# step_motor.net
KiCad netlist of a schematic drawn in EAGLE
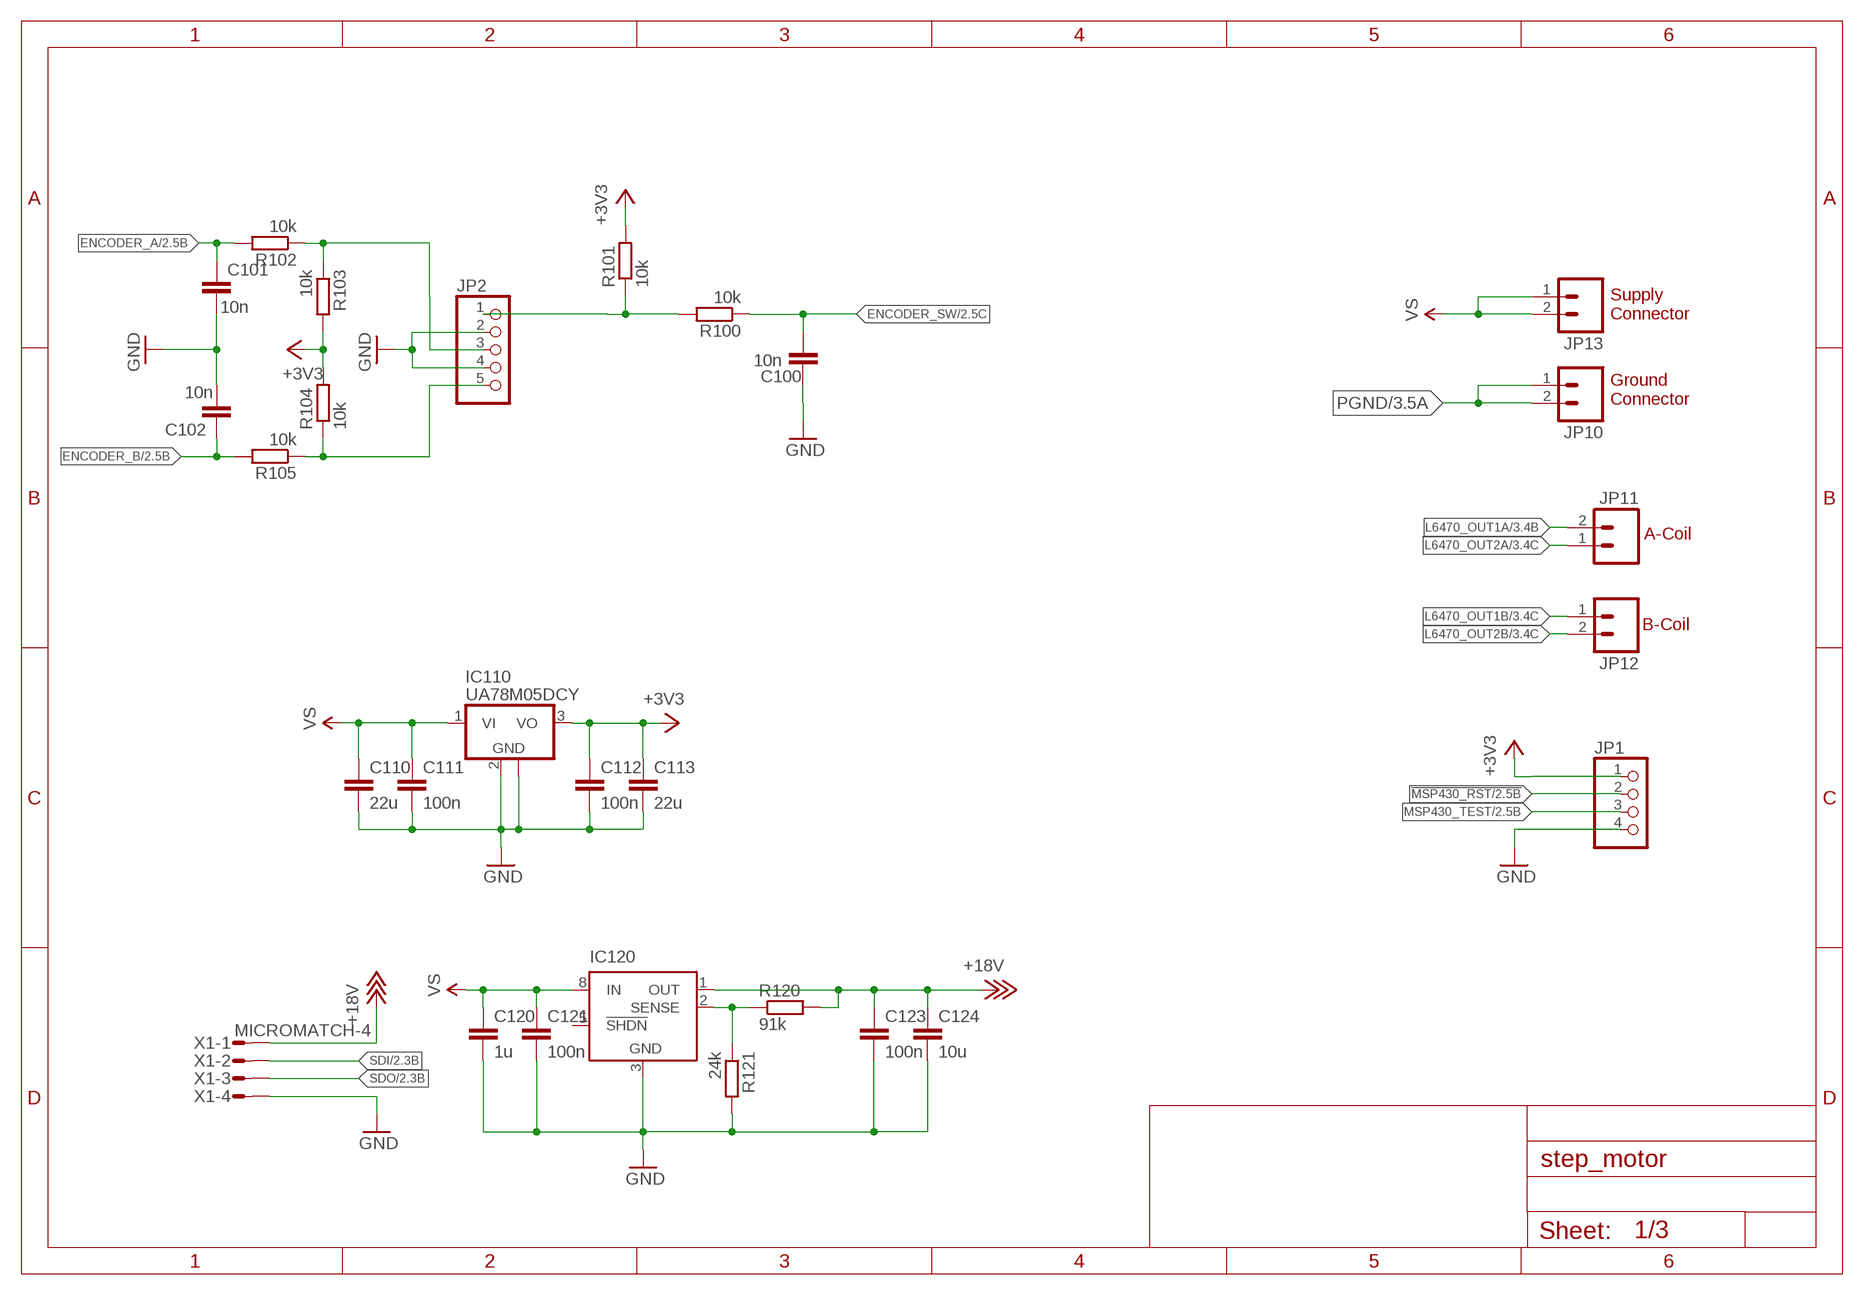
[diagram p0: schematic, sheet 1]
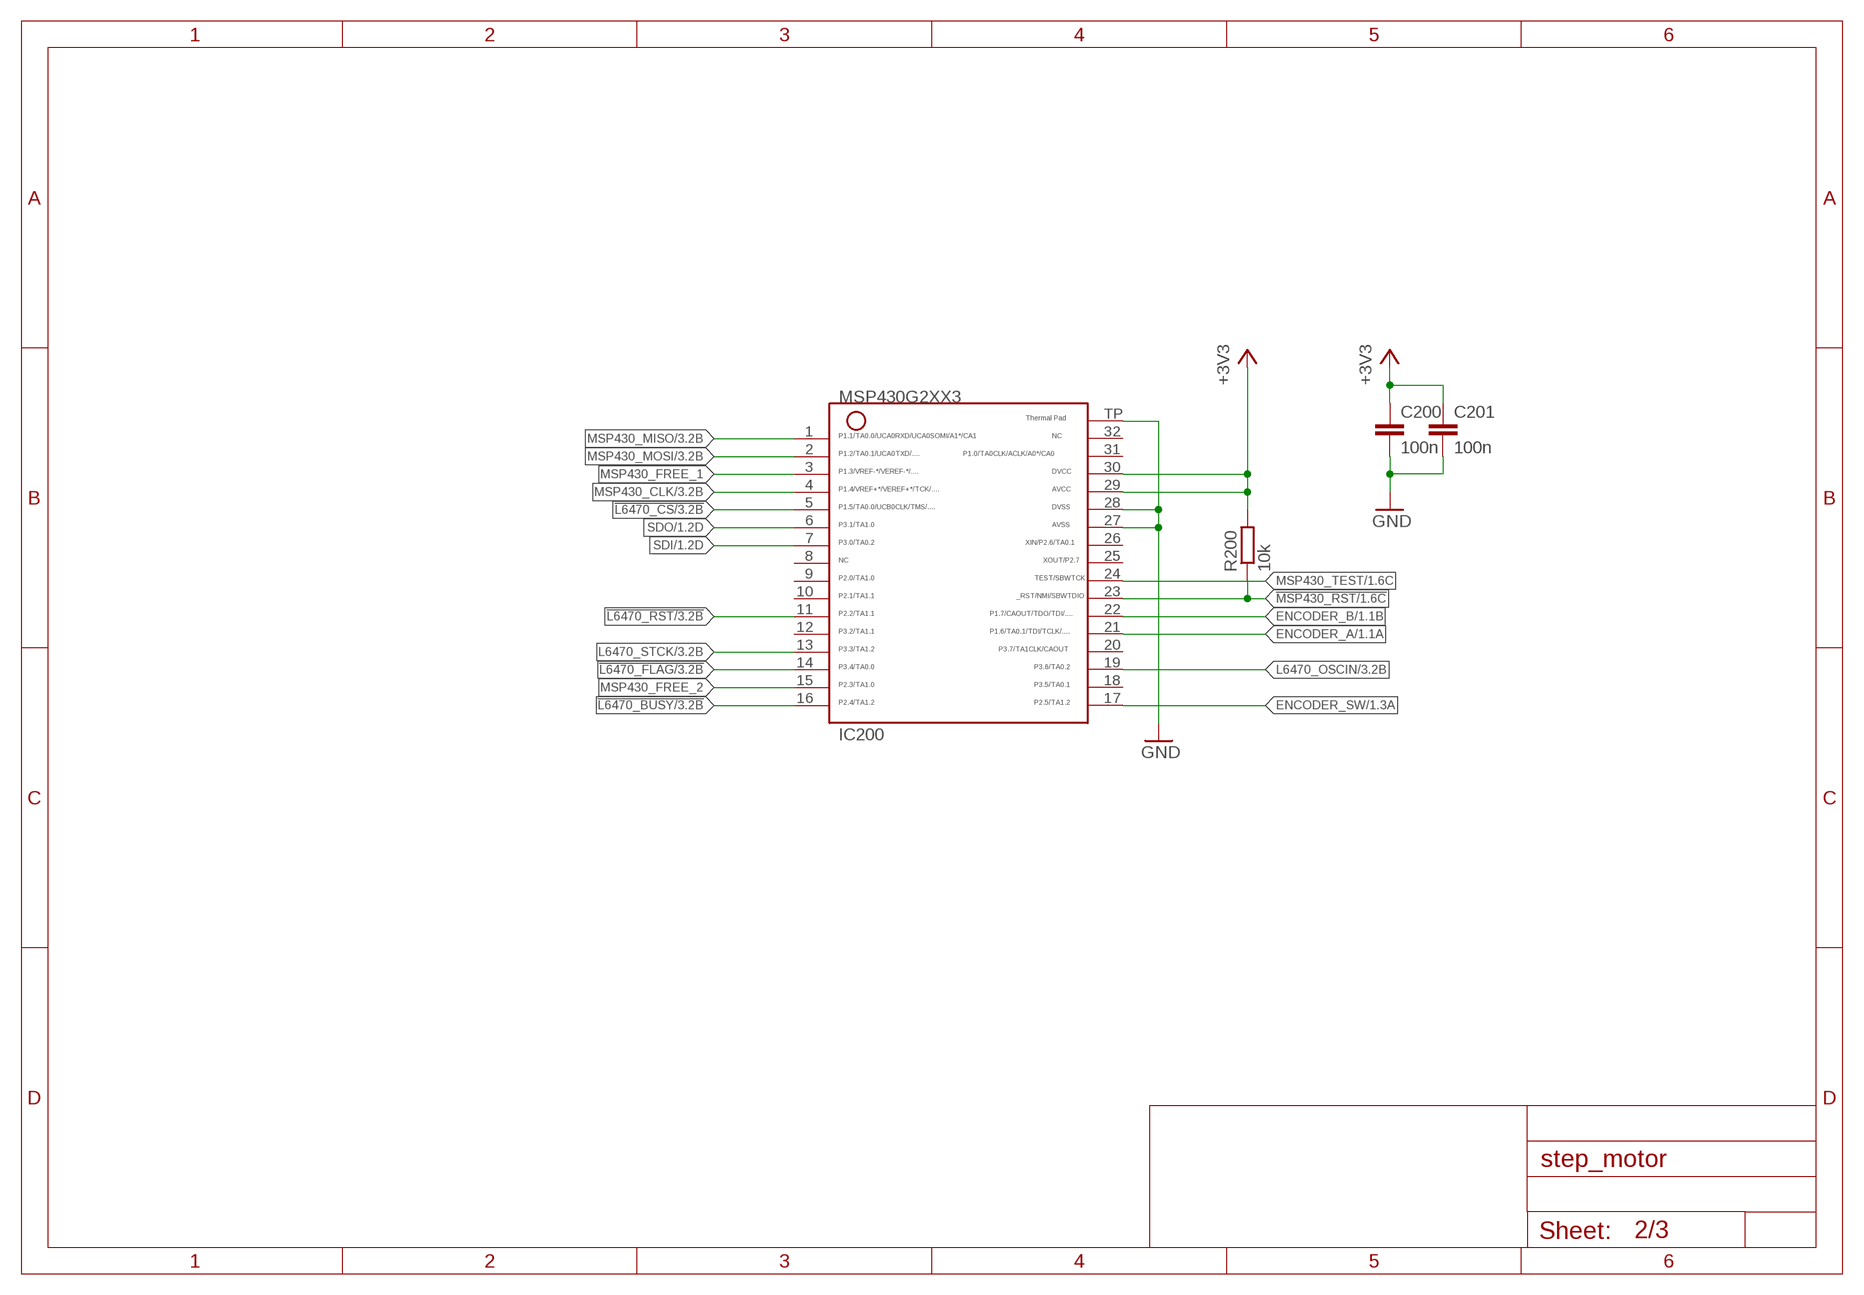
[diagram p1: schematic, sheet 2]
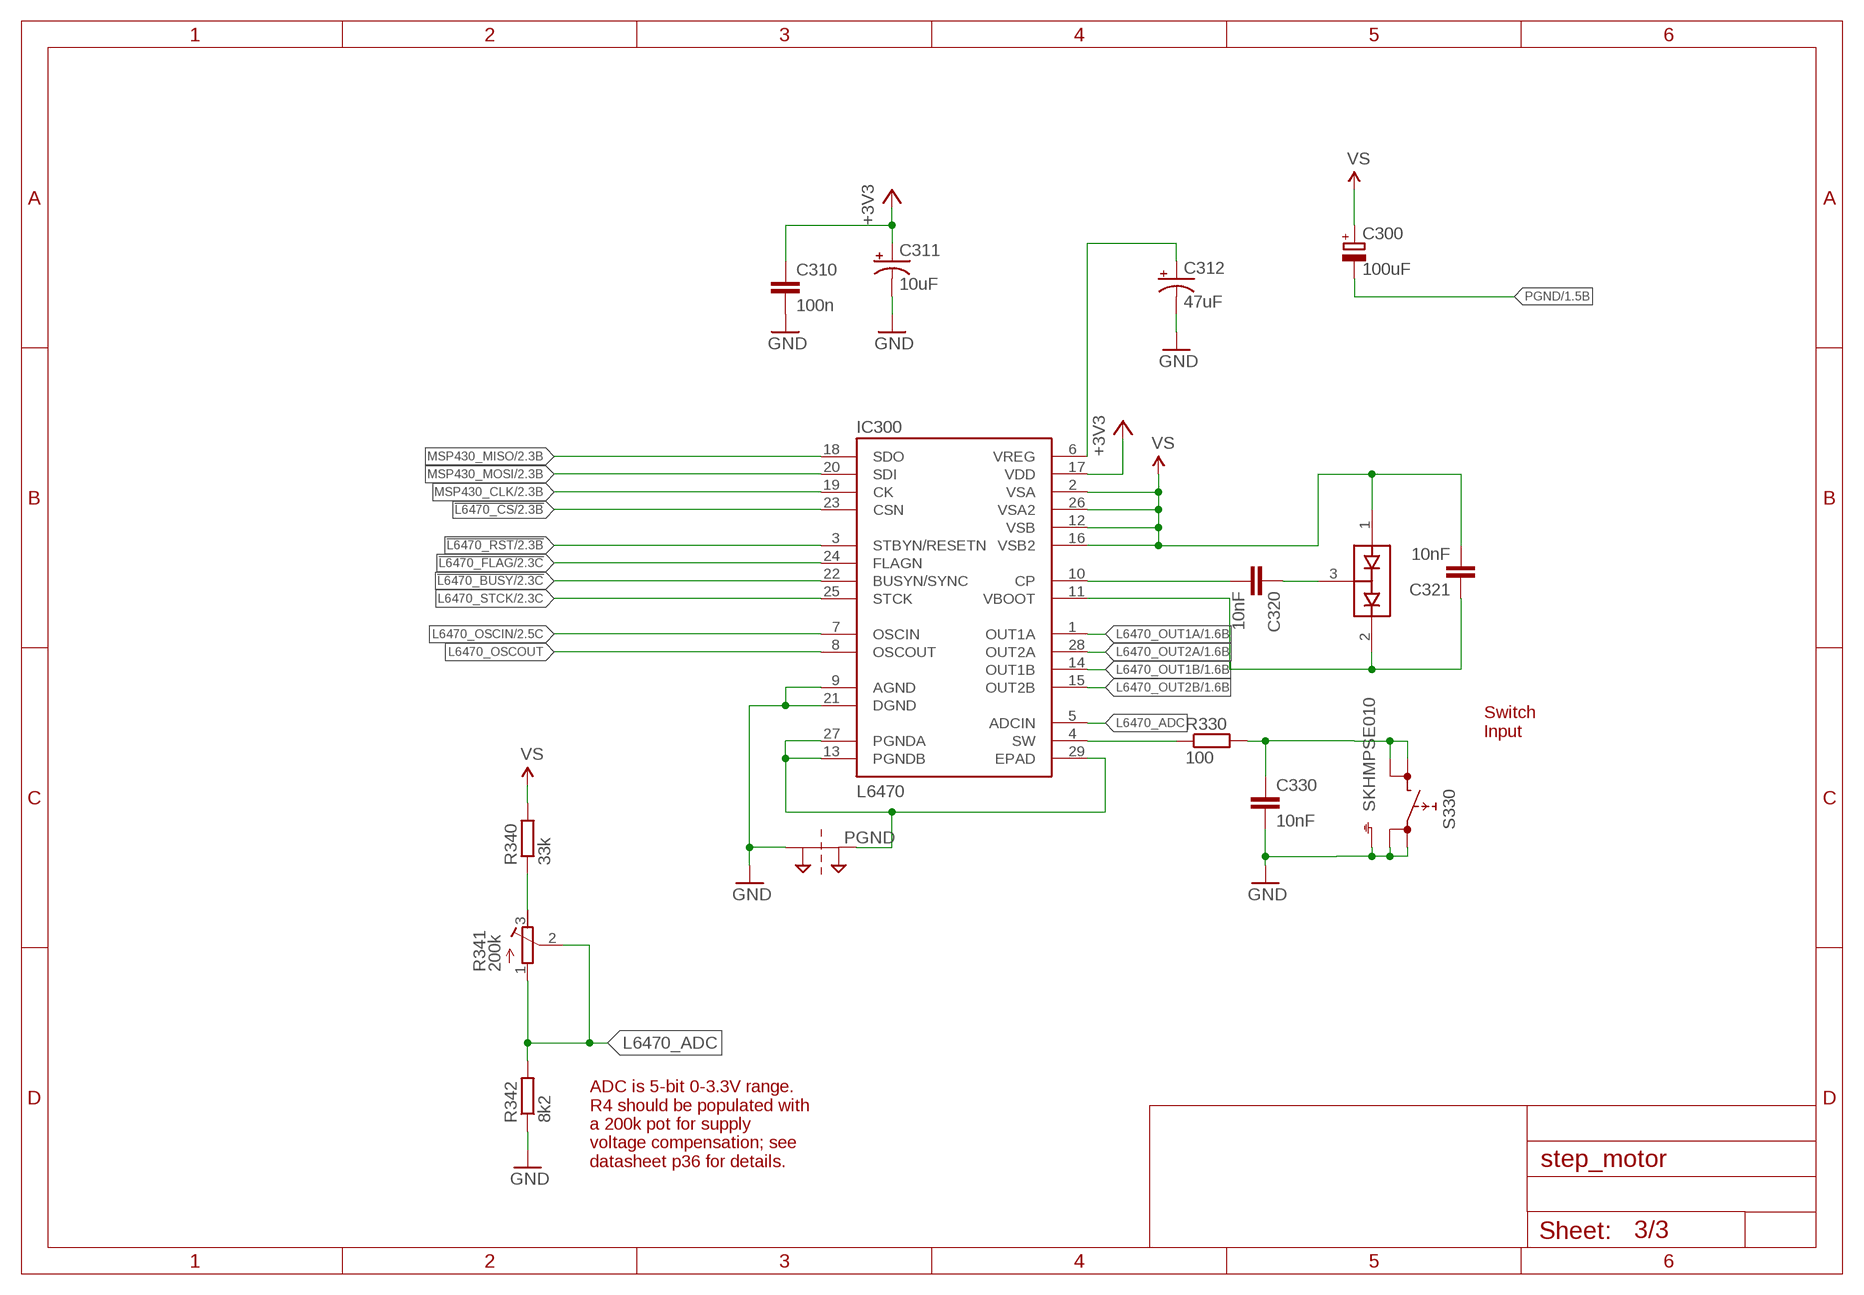
[diagram p2: schematic, sheet 3]

(export (version "E")
  (design (tool "Eeschema 10.0.6"))
  (components
    (comp (ref "C100")
      (value "10n")
      (footprint "eagle-import:C0603")
      (libsource (lib "eagle-import") (part "C-EUC0603"))
    )
    (comp (ref "C101")
      (value "10n")
      (footprint "eagle-import:C0603")
      (libsource (lib "eagle-import") (part "C-EUC0603"))
    )
    (comp (ref "C102")
      (value "10n")
      (footprint "eagle-import:C0603")
      (libsource (lib "eagle-import") (part "C-EUC0603"))
    )
    (comp (ref "C110")
      (value "22u")
      (footprint "eagle-import:C1206")
      (libsource (lib "eagle-import") (part "C-EUC1206"))
    )
    (comp (ref "C111")
      (value "100n")
      (footprint "eagle-import:C0603")
      (libsource (lib "eagle-import") (part "C-EUC0603"))
    )
    (comp (ref "C112")
      (value "100n")
      (footprint "eagle-import:C0603")
      (libsource (lib "eagle-import") (part "C-EUC0603"))
    )
    (comp (ref "C113")
      (value "22u")
      (footprint "eagle-import:C1206")
      (libsource (lib "eagle-import") (part "C-EUC1206"))
    )
    (comp (ref "C120")
      (value "1u")
      (footprint "eagle-import:C1206")
      (libsource (lib "eagle-import") (part "C-EUC1206"))
    )
    (comp (ref "C121")
      (value "100n")
      (footprint "eagle-import:C0603")
      (libsource (lib "eagle-import") (part "C-EUC0603"))
    )
    (comp (ref "C123")
      (value "100n")
      (footprint "eagle-import:C0603")
      (libsource (lib "eagle-import") (part "C-EUC0603"))
    )
    (comp (ref "C124")
      (value "10u")
      (footprint "eagle-import:C1206")
      (libsource (lib "eagle-import") (part "C-EUC1206"))
    )
    (comp (ref "IC110")
      (value "UA78M05DCY")
      (footprint "eagle-import:SOT223")
      (libsource (lib "eagle-import") (part "UA78MDCY05"))
    )
    (comp (ref "IC120")
      (value "LT1129CS8")
      (footprint "eagle-import:SOIC8")
      (fields (field (name "MPN") "LT1129CS8-5#PBF"))
      (libsource (lib "eagle-import") (part "LT1129CS8"))
    )
    (comp (ref "JP1")
      (value "PINHD-1X4")
      (footprint "eagle-import:1X04")
      (libsource (lib "eagle-import") (part "PINHD-1X4"))
    )
    (comp (ref "JP2")
      (value "PINHD-1X5")
      (footprint "eagle-import:1X05")
      (libsource (lib "eagle-import") (part "PINHD-1X5"))
    )
    (comp (ref "JP10")
      (value "M023.5MM")
      (footprint "eagle-import:SCREWTERMINAL-3.5MM-2")
      (libsource (lib "eagle-import") (part "M023.5MM"))
    )
    (comp (ref "JP11")
      (value "M023.5MM")
      (footprint "eagle-import:SCREWTERMINAL-3.5MM-2")
      (libsource (lib "eagle-import") (part "M023.5MM"))
    )
    (comp (ref "JP12")
      (value "M023.5MM")
      (footprint "eagle-import:SCREWTERMINAL-3.5MM-2")
      (libsource (lib "eagle-import") (part "M023.5MM"))
    )
    (comp (ref "JP13")
      (value "M023.5MM")
      (footprint "eagle-import:SCREWTERMINAL-3.5MM-2")
      (libsource (lib "eagle-import") (part "M023.5MM"))
    )
    (comp (ref "R100")
      (value "10k")
      (footprint "eagle-import:R0603")
      (libsource (lib "eagle-import") (part "R-EU_R0603"))
    )
    (comp (ref "R101")
      (value "10k")
      (footprint "eagle-import:R0603")
      (libsource (lib "eagle-import") (part "R-EU_R0603"))
    )
    (comp (ref "R102")
      (value "10k")
      (footprint "eagle-import:R0603")
      (libsource (lib "eagle-import") (part "R-EU_R0603"))
    )
    (comp (ref "R103")
      (value "10k")
      (footprint "eagle-import:R0603")
      (libsource (lib "eagle-import") (part "R-EU_R0603"))
    )
    (comp (ref "R104")
      (value "10k")
      (footprint "eagle-import:R0603")
      (libsource (lib "eagle-import") (part "R-EU_R0603"))
    )
    (comp (ref "R105")
      (value "10k")
      (footprint "eagle-import:R0603")
      (libsource (lib "eagle-import") (part "R-EU_R0603"))
    )
    (comp (ref "R120")
      (value "91k")
      (footprint "eagle-import:R0603")
      (libsource (lib "eagle-import") (part "R-EU_R0603"))
    )
    (comp (ref "R121")
      (value "24k")
      (footprint "eagle-import:R0603")
      (libsource (lib "eagle-import") (part "R-EU_R0603"))
    )
    (comp (ref "X1")
      (value "MICROMATCH-4")
      (footprint "eagle-import:MICROMATCH-4")
      (fields (field (name "MPN") "7-215464-4"))
      (libsource (lib "eagle-import") (part "MICROMATCH-4"))
    )
    (comp (ref "C200")
      (value "100n")
      (footprint "eagle-import:C0603")
      (libsource (lib "eagle-import") (part "C-EUC0603"))
    )
    (comp (ref "C201")
      (value "100n")
      (footprint "eagle-import:C0603")
      (libsource (lib "eagle-import") (part "C-EUC0603"))
    )
    (comp (ref "IC200")
      (value "G2XX3---RHB32")
      (footprint "eagle-import:RHB32")
      (libsource (lib "eagle-import") (part "G2XX3---RHB32"))
    )
    (comp (ref "R200")
      (value "10k")
      (footprint "eagle-import:R0603")
      (libsource (lib "eagle-import") (part "R-EU_R0603"))
    )
    (comp (ref "C300")
      (value "100uF")
      (footprint "eagle-import:PANASONIC_D")
      (libsource (lib "eagle-import") (part "CPOL-EUD"))
    )
    (comp (ref "C310")
      (value "100n")
      (footprint "eagle-import:C0603")
      (libsource (lib "eagle-import") (part "C-EUC0603"))
    )
    (comp (ref "C311")
      (value "10uF")
      (footprint "eagle-import:EIA3216")
      (libsource (lib "eagle-import") (part "10UF-TANT"))
    )
    (comp (ref "C312")
      (value "47uF")
      (footprint "eagle-import:EIA3528")
      (libsource (lib "eagle-import") (part "47UF-TANT"))
    )
    (comp (ref "C320")
      (value "10nF")
      (footprint "eagle-import:C0603")
      (libsource (lib "eagle-import") (part "C-EUC0603"))
    )
    (comp (ref "C321")
      (value "10nF")
      (footprint "eagle-import:C0603")
      (libsource (lib "eagle-import") (part "C-EUC0603"))
    )
    (comp (ref "C330")
      (value "10nF")
      (footprint "eagle-import:C0603")
      (libsource (lib "eagle-import") (part "C-EUC0603"))
    )
    (comp (ref "D320")
      (value "BAV99")
      (footprint "eagle-import:SOT23")
      (libsource (lib "eagle-import") (part "BAV99"))
    )
    (comp (ref "IC300")
      (value "L6470")
      (footprint "eagle-import:HTSSOP28")
      (libsource (lib "eagle-import") (part "L6470"))
    )
    (comp (ref "R330")
      (value "100")
      (footprint "eagle-import:R0603")
      (libsource (lib "eagle-import") (part "R-EU_R0603"))
    )
    (comp (ref "R340")
      (value "33k")
      (footprint "eagle-import:R0603")
      (libsource (lib "eagle-import") (part "R-EU_R0603"))
    )
    (comp (ref "R341")
      (value "200k")
      (footprint "eagle-import:RTRIM3224X")
      (libsource (lib "eagle-import") (part "R-TRIMM3224X"))
    )
    (comp (ref "R342")
      (value "8k2")
      (footprint "eagle-import:R0603")
      (libsource (lib "eagle-import") (part "R-EU_R0603"))
    )
    (comp (ref "S330")
      (value "SKHMPSE010")
      (footprint "eagle-import:SKHMPXE010")
      (libsource (lib "eagle-import") (part "SKHMPE010S"))
    )
    (comp (ref "SJ2")
      (value "2PT_GND_TIE")
      (footprint "eagle-import:2PT_GND_TIE")
      (libsource (lib "eagle-import") (part "2PT_GND_TIE"))
    )
  )
  (nets
    (net (code "1") (name "+3V3") (class "Default")
      (node (ref "C112") (pin "1") (pinfunction "1_1") (pintype "passive"))
      (node (ref "C113") (pin "1") (pinfunction "1_1") (pintype "passive"))
      (node (ref "C200") (pin "1") (pinfunction "1_1") (pintype "passive"))
      (node (ref "C201") (pin "1") (pinfunction "1_1") (pintype "passive"))
      (node (ref "C310") (pin "1") (pinfunction "1_1") (pintype "passive"))
      (node (ref "C311") (pin "A") (pinfunction "+_A") (pintype "passive"))
      (node (ref "IC110") (pin "3") (pinfunction "VO_3") (pintype "passive"))
      (node (ref "IC200") (pin "29") (pinfunction "29_29") (pintype "bidirectional"))
      (node (ref "IC200") (pin "30") (pinfunction "30_30") (pintype "bidirectional"))
      (node (ref "IC300") (pin "17") (pinfunction "VDD_17") (pintype "bidirectional"))
      (node (ref "JP1") (pin "1") (pinfunction "1_1") (pintype "passive"))
      (node (ref "R101") (pin "2") (pinfunction "2_2") (pintype "passive"))
      (node (ref "R103") (pin "2") (pinfunction "2_2") (pintype "passive"))
      (node (ref "R104") (pin "2") (pinfunction "2_2") (pintype "passive"))
      (node (ref "R200") (pin "2") (pinfunction "2_2") (pintype "passive"))
    )
    (net (code "2") (name "+18V") (class "Default")
      (node (ref "C123") (pin "1") (pinfunction "1_1") (pintype "passive"))
      (node (ref "C124") (pin "1") (pinfunction "1_1") (pintype "passive"))
      (node (ref "IC120") (pin "1") (pinfunction "OUT_1") (pintype "output"))
      (node (ref "R120") (pin "2") (pinfunction "2_2") (pintype "passive"))
      (node (ref "X1") (pin "1") (pinfunction "S_1") (pintype "passive"))
    )
    (net (code "3") (name "ENCODER_A") (class "Default")
      (node (ref "C101") (pin "1") (pinfunction "1_1") (pintype "passive"))
      (node (ref "IC200") (pin "21") (pinfunction "21_21") (pintype "bidirectional"))
      (node (ref "R102") (pin "2") (pinfunction "2_2") (pintype "passive"))
    )
    (net (code "4") (name "ENCODER_B") (class "Default")
      (node (ref "C102") (pin "1") (pinfunction "1_1") (pintype "passive"))
      (node (ref "IC200") (pin "22") (pinfunction "22_22") (pintype "bidirectional"))
      (node (ref "R105") (pin "2") (pinfunction "2_2") (pintype "passive"))
    )
    (net (code "5") (name "ENCODER_SW") (class "Default")
      (node (ref "C100") (pin "2") (pinfunction "2_2") (pintype "passive"))
      (node (ref "IC200") (pin "17") (pinfunction "17_17") (pintype "bidirectional"))
      (node (ref "R100") (pin "1") (pinfunction "1_1") (pintype "passive"))
    )
    (net (code "6") (name "GND") (class "Default")
      (node (ref "C100") (pin "1") (pinfunction "1_1") (pintype "passive"))
      (node (ref "C101") (pin "2") (pinfunction "2_2") (pintype "passive"))
      (node (ref "C102") (pin "2") (pinfunction "2_2") (pintype "passive"))
      (node (ref "C110") (pin "2") (pinfunction "2_2") (pintype "passive"))
      (node (ref "C111") (pin "2") (pinfunction "2_2") (pintype "passive"))
      (node (ref "C112") (pin "2") (pinfunction "2_2") (pintype "passive"))
      (node (ref "C113") (pin "2") (pinfunction "2_2") (pintype "passive"))
      (node (ref "C120") (pin "2") (pinfunction "2_2") (pintype "passive"))
      (node (ref "C121") (pin "2") (pinfunction "2_2") (pintype "passive"))
      (node (ref "C123") (pin "2") (pinfunction "2_2") (pintype "passive"))
      (node (ref "C124") (pin "2") (pinfunction "2_2") (pintype "passive"))
      (node (ref "C200") (pin "2") (pinfunction "2_2") (pintype "passive"))
      (node (ref "C201") (pin "2") (pinfunction "2_2") (pintype "passive"))
      (node (ref "C310") (pin "2") (pinfunction "2_2") (pintype "passive"))
      (node (ref "C311") (pin "C") (pinfunction "-_C") (pintype "passive"))
      (node (ref "C312") (pin "C") (pinfunction "-_C") (pintype "passive"))
      (node (ref "C330") (pin "2") (pinfunction "2_2") (pintype "passive"))
      (node (ref "IC110") (pin "2") (pinfunction "GND_2") (pintype "passive"))
      (node (ref "IC110") (pin "4") (pinfunction "GND_4") (pintype "passive"))
      (node (ref "IC120") (pin "3") (pinfunction "GND_3") (pintype "power_in"))
      (node (ref "IC200") (pin "27") (pinfunction "27_27") (pintype "bidirectional"))
      (node (ref "IC200") (pin "28") (pinfunction "28_28") (pintype "bidirectional"))
      (node (ref "IC200") (pin "TP") (pinfunction "TP_TP") (pintype "bidirectional"))
      (node (ref "IC300") (pin "21") (pinfunction "DGND_21") (pintype "bidirectional"))
      (node (ref "IC300") (pin "9") (pinfunction "AGND_9") (pintype "bidirectional"))
      (node (ref "JP1") (pin "4") (pinfunction "4_4") (pintype "passive"))
      (node (ref "JP2") (pin "2") (pinfunction "2_2") (pintype "passive"))
      (node (ref "JP2") (pin "4") (pinfunction "4_4") (pintype "passive"))
      (node (ref "R121") (pin "2") (pinfunction "2_2") (pintype "passive"))
      (node (ref "R342") (pin "1") (pinfunction "1_1") (pintype "passive"))
      (node (ref "S330") (pin "1") (pinfunction "1.1_1") (pintype "passive"))
      (node (ref "S330") (pin "2") (pinfunction "1.2_2") (pintype "passive"))
      (node (ref "S330") (pin "5") (pinfunction "SH_5") (pintype "passive"))
      (node (ref "SJ2") (pin "P$1") (pinfunction "P$1_P$1") (pintype "bidirectional"))
      (node (ref "X1") (pin "4") (pinfunction "S_4") (pintype "passive"))
    )
    (net (code "7") (name "L6470_ADC") (class "Default")
      (node (ref "IC300") (pin "5") (pinfunction "ADCIN_5") (pintype "bidirectional"))
      (node (ref "R341") (pin "1") (pinfunction "A_1") (pintype "passive"))
      (node (ref "R341") (pin "2") (pinfunction "S_2") (pintype "passive"))
      (node (ref "R342") (pin "2") (pinfunction "2_2") (pintype "passive"))
    )
    (net (code "8") (name "L6470_OSCIN") (class "Default")
      (node (ref "IC200") (pin "19") (pinfunction "19_19") (pintype "bidirectional"))
      (node (ref "IC300") (pin "7") (pinfunction "OSCIN_7") (pintype "bidirectional"))
    )
    (net (code "9") (name "L6470_OSCOUT") (class "Default")
      (node (ref "IC300") (pin "8") (pinfunction "OSCOUT_8") (pintype "bidirectional"))
    )
    (net (code "10") (name "L6470_OUT1A") (class "Default")
      (node (ref "IC300") (pin "1") (pinfunction "OUT1A_1") (pintype "bidirectional"))
      (node (ref "JP11") (pin "2") (pinfunction "2_2") (pintype "passive"))
    )
    (net (code "11") (name "L6470_OUT1B") (class "Default")
      (node (ref "IC300") (pin "14") (pinfunction "OUT1B_14") (pintype "bidirectional"))
      (node (ref "JP12") (pin "1") (pinfunction "1_1") (pintype "passive"))
    )
    (net (code "12") (name "L6470_OUT2A") (class "Default")
      (node (ref "IC300") (pin "28") (pinfunction "OUT2A_28") (pintype "bidirectional"))
      (node (ref "JP11") (pin "1") (pinfunction "1_1") (pintype "passive"))
    )
    (net (code "13") (name "L6470_OUT2B") (class "Default")
      (node (ref "IC300") (pin "15") (pinfunction "OUT2B_15") (pintype "bidirectional"))
      (node (ref "JP12") (pin "2") (pinfunction "2_2") (pintype "passive"))
    )
    (net (code "14") (name "L6470_STCK") (class "Default")
      (node (ref "IC200") (pin "13") (pinfunction "13_13") (pintype "bidirectional"))
      (node (ref "IC300") (pin "25") (pinfunction "STCK_25") (pintype "bidirectional"))
    )
    (net (code "15") (name "MSP430_CLK") (class "Default")
      (node (ref "IC200") (pin "4") (pinfunction "4_4") (pintype "bidirectional"))
      (node (ref "IC300") (pin "19") (pinfunction "CK_19") (pintype "bidirectional"))
    )
    (net (code "16") (name "MSP430_FREE_1") (class "Default")
      (node (ref "IC200") (pin "3") (pinfunction "3_3") (pintype "bidirectional"))
    )
    (net (code "17") (name "MSP430_FREE_2") (class "Default")
      (node (ref "IC200") (pin "15") (pinfunction "15_15") (pintype "bidirectional"))
    )
    (net (code "18") (name "MSP430_MISO") (class "Default")
      (node (ref "IC200") (pin "1") (pinfunction "1_1") (pintype "bidirectional"))
      (node (ref "IC300") (pin "18") (pinfunction "SDO_18") (pintype "bidirectional"))
    )
    (net (code "19") (name "MSP430_MOSI") (class "Default")
      (node (ref "IC200") (pin "2") (pinfunction "2_2") (pintype "bidirectional"))
      (node (ref "IC300") (pin "20") (pinfunction "SDI_20") (pintype "bidirectional"))
    )
    (net (code "20") (name "MSP430_TEST") (class "Default")
      (node (ref "IC200") (pin "24") (pinfunction "24_24") (pintype "bidirectional"))
      (node (ref "JP1") (pin "3") (pinfunction "3_3") (pintype "passive"))
    )
    (net (code "21") (name "Net-(C312-+)") (class "Default")
      (node (ref "C312") (pin "A") (pinfunction "+_A") (pintype "passive"))
      (node (ref "IC300") (pin "6") (pinfunction "VREG_6") (pintype "bidirectional"))
    )
    (net (code "22") (name "Net-(D320-C2)") (class "Default")
      (node (ref "C321") (pin "1") (pinfunction "1_1") (pintype "passive"))
      (node (ref "D320") (pin "2") (pinfunction "C2_2") (pintype "bidirectional"))
      (node (ref "IC300") (pin "11") (pinfunction "VBOOT_11") (pintype "bidirectional"))
    )
    (net (code "23") (name "Net-(D320-COM)") (class "Default")
      (node (ref "C320") (pin "1") (pinfunction "1_1") (pintype "passive"))
      (node (ref "D320") (pin "3") (pinfunction "COM_3") (pintype "bidirectional"))
    )
    (net (code "24") (name "Net-(IC120A-SENSE)") (class "Default")
      (node (ref "IC120") (pin "2") (pinfunction "SENSE_2") (pintype "input"))
      (node (ref "R120") (pin "1") (pinfunction "1_1") (pintype "passive"))
      (node (ref "R121") (pin "1") (pinfunction "1_1") (pintype "passive"))
    )
    (net (code "25") (name "Net-(IC300-CP)") (class "Default")
      (node (ref "C320") (pin "2") (pinfunction "2_2") (pintype "passive"))
      (node (ref "IC300") (pin "10") (pinfunction "CP_10") (pintype "bidirectional"))
    )
    (net (code "26") (name "Net-(IC300-SW)") (class "Default")
      (node (ref "IC300") (pin "4") (pinfunction "SW_4") (pintype "bidirectional"))
      (node (ref "R330") (pin "1") (pinfunction "1_1") (pintype "passive"))
    )
    (net (code "27") (name "Net-(JP2-Pad1)") (class "Default")
      (node (ref "JP2") (pin "1") (pinfunction "1_1") (pintype "passive"))
      (node (ref "R100") (pin "2") (pinfunction "2_2") (pintype "passive"))
      (node (ref "R101") (pin "1") (pinfunction "1_1") (pintype "passive"))
    )
    (net (code "28") (name "Net-(JP2-Pad3)") (class "Default")
      (node (ref "JP2") (pin "3") (pinfunction "3_3") (pintype "passive"))
      (node (ref "R102") (pin "1") (pinfunction "1_1") (pintype "passive"))
      (node (ref "R103") (pin "1") (pinfunction "1_1") (pintype "passive"))
    )
    (net (code "29") (name "Net-(JP2-Pad5)") (class "Default")
      (node (ref "JP2") (pin "5") (pinfunction "5_5") (pintype "passive"))
      (node (ref "R104") (pin "1") (pinfunction "1_1") (pintype "passive"))
      (node (ref "R105") (pin "1") (pinfunction "1_1") (pintype "passive"))
    )
    (net (code "30") (name "Net-(R341-E)") (class "Default")
      (node (ref "R340") (pin "1") (pinfunction "1_1") (pintype "passive"))
      (node (ref "R341") (pin "3") (pinfunction "E_3") (pintype "passive"))
    )
    (net (code "31") (name "Net-(S330-2.1)") (class "Default")
      (node (ref "C330") (pin "1") (pinfunction "1_1") (pintype "passive"))
      (node (ref "R330") (pin "2") (pinfunction "2_2") (pintype "passive"))
      (node (ref "S330") (pin "3") (pinfunction "2.1_3") (pintype "passive"))
      (node (ref "S330") (pin "4") (pinfunction "2.2_4") (pintype "passive"))
    )
    (net (code "32") (name "PGND") (class "Default")
      (node (ref "C300") (pin "-") (pinfunction "-_-") (pintype "passive"))
      (node (ref "IC300") (pin "13") (pinfunction "PGNDB_13") (pintype "bidirectional"))
      (node (ref "IC300") (pin "27") (pinfunction "PGNDA_27") (pintype "bidirectional"))
      (node (ref "IC300") (pin "29") (pinfunction "EPAD_29") (pintype "bidirectional"))
      (node (ref "JP10") (pin "1") (pinfunction "1_1") (pintype "passive"))
      (node (ref "JP10") (pin "2") (pinfunction "2_2") (pintype "passive"))
      (node (ref "SJ2") (pin "P$2") (pinfunction "P$2_P$2") (pintype "bidirectional"))
    )
    (net (code "33") (name "SDI") (class "Default")
      (node (ref "IC200") (pin "7") (pinfunction "7_7") (pintype "bidirectional"))
      (node (ref "X1") (pin "2") (pinfunction "S_2") (pintype "passive"))
    )
    (net (code "34") (name "SDO") (class "Default")
      (node (ref "IC200") (pin "6") (pinfunction "6_6") (pintype "bidirectional"))
      (node (ref "X1") (pin "3") (pinfunction "S_3") (pintype "passive"))
    )
    (net (code "35") (name "VS") (class "Default")
      (node (ref "C110") (pin "1") (pinfunction "1_1") (pintype "passive"))
      (node (ref "C111") (pin "1") (pinfunction "1_1") (pintype "passive"))
      (node (ref "C120") (pin "1") (pinfunction "1_1") (pintype "passive"))
      (node (ref "C121") (pin "1") (pinfunction "1_1") (pintype "passive"))
      (node (ref "C300") (pin "+") (pinfunction "+_+") (pintype "passive"))
      (node (ref "C321") (pin "2") (pinfunction "2_2") (pintype "passive"))
      (node (ref "D320") (pin "1") (pinfunction "A1_1") (pintype "bidirectional"))
      (node (ref "IC110") (pin "1") (pinfunction "VI_1") (pintype "input"))
      (node (ref "IC120") (pin "8") (pinfunction "IN_8") (pintype "input"))
      (node (ref "IC300") (pin "12") (pinfunction "VSB_12") (pintype "bidirectional"))
      (node (ref "IC300") (pin "16") (pinfunction "VSB2_16") (pintype "bidirectional"))
      (node (ref "IC300") (pin "2") (pinfunction "VSA_2") (pintype "bidirectional"))
      (node (ref "IC300") (pin "26") (pinfunction "VSA2_26") (pintype "bidirectional"))
      (node (ref "JP13") (pin "1") (pinfunction "1_1") (pintype "passive"))
      (node (ref "JP13") (pin "2") (pinfunction "2_2") (pintype "passive"))
      (node (ref "R340") (pin "2") (pinfunction "2_2") (pintype "passive"))
    )
    (net (code "36") (name "unconnected-(IC120A-~{SHDN}-Pad5)") (class "Default")
      (node (ref "IC120") (pin "5") (pinfunction "~{SHDN}_5") (pintype "input"))
    )
    (net (code "37") (name "unconnected-(IC200-Pad8)") (class "Default")
      (node (ref "IC200") (pin "8") (pinfunction "8_8") (pintype "bidirectional"))
    )
    (net (code "38") (name "unconnected-(IC200-Pad9)") (class "Default")
      (node (ref "IC200") (pin "9") (pinfunction "9_9") (pintype "bidirectional"))
    )
    (net (code "39") (name "unconnected-(IC200-Pad10)") (class "Default")
      (node (ref "IC200") (pin "10") (pinfunction "10_10") (pintype "bidirectional"))
    )
    (net (code "40") (name "unconnected-(IC200-Pad12)") (class "Default")
      (node (ref "IC200") (pin "12") (pinfunction "12_12") (pintype "bidirectional"))
    )
    (net (code "41") (name "unconnected-(IC200-Pad18)") (class "Default")
      (node (ref "IC200") (pin "18") (pinfunction "18_18") (pintype "bidirectional"))
    )
    (net (code "42") (name "unconnected-(IC200-Pad20)") (class "Default")
      (node (ref "IC200") (pin "20") (pinfunction "20_20") (pintype "bidirectional"))
    )
    (net (code "43") (name "unconnected-(IC200-Pad25)") (class "Default")
      (node (ref "IC200") (pin "25") (pinfunction "25_25") (pintype "bidirectional"))
    )
    (net (code "44") (name "unconnected-(IC200-Pad26)") (class "Default")
      (node (ref "IC200") (pin "26") (pinfunction "26_26") (pintype "bidirectional"))
    )
    (net (code "45") (name "unconnected-(IC200-Pad31)") (class "Default")
      (node (ref "IC200") (pin "31") (pinfunction "31_31") (pintype "bidirectional"))
    )
    (net (code "46") (name "unconnected-(IC200-Pad32)") (class "Default")
      (node (ref "IC200") (pin "32") (pinfunction "32_32") (pintype "bidirectional"))
    )
    (net (code "47") (name "~{L6470_BUSY}") (class "Default")
      (node (ref "IC200") (pin "16") (pinfunction "16_16") (pintype "bidirectional"))
      (node (ref "IC300") (pin "22") (pinfunction "BUSYN/SYNC_22") (pintype "bidirectional"))
    )
    (net (code "48") (name "~{L6470_CS}") (class "Default")
      (node (ref "IC200") (pin "5") (pinfunction "5_5") (pintype "bidirectional"))
      (node (ref "IC300") (pin "23") (pinfunction "CSN_23") (pintype "bidirectional"))
    )
    (net (code "49") (name "~{L6470_FLAG}") (class "Default")
      (node (ref "IC200") (pin "14") (pinfunction "14_14") (pintype "bidirectional"))
      (node (ref "IC300") (pin "24") (pinfunction "FLAGN_24") (pintype "bidirectional"))
    )
    (net (code "50") (name "~{L6470_RST}") (class "Default")
      (node (ref "IC200") (pin "11") (pinfunction "11_11") (pintype "bidirectional"))
      (node (ref "IC300") (pin "3") (pinfunction "STBYN/RESETN_3") (pintype "bidirectional"))
    )
    (net (code "51") (name "~{MSP430_RST}") (class "Default")
      (node (ref "IC200") (pin "23") (pinfunction "23_23") (pintype "bidirectional"))
      (node (ref "JP1") (pin "2") (pinfunction "2_2") (pintype "passive"))
      (node (ref "R200") (pin "1") (pinfunction "1_1") (pintype "passive"))
    )
  )
)
